# LevelTranslator.net
KiCad netlist of a schematic drawn in Altium Designer
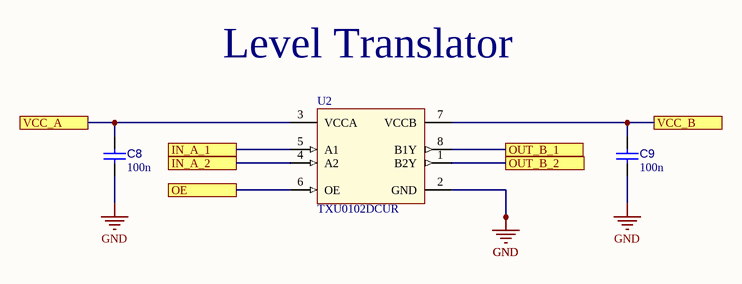
[diagram p0: LevelTranslator.SchDoc]

(export (version "E")
  (design (tool "Eeschema 10.0.6"))
  (components
    (comp (ref "C8")
      (value "100n")
      (footprint "C_1608[0603]")
      (description "Capacitor type 1")
      (fields (field (name "TOLERANCE") "10%") (field (name "Comment") "CAP CER 100nF 50V 0603"))
      (libsource (lib "TEP-AltiumLib-Passives-RLC") (part "capacitor"))
    )
    (comp (ref "C9")
      (value "100n")
      (footprint "C_1608[0603]")
      (description "Capacitor type 1")
      (fields (field (name "TOLERANCE") "10%") (field (name "Comment") "CAP CER 100nF 50V 0603"))
      (libsource (lib "TEP-AltiumLib-Passives-RLC") (part "capacitor"))
    )
    (comp (ref "U2")
      (value "TXU0102DCUR")
      (footprint "U_VSSOP50P310X200X90-8N")
      (description "Two channel fixed-direction level shifter 8-VSSOP")
      (libsource (lib "TEP-AltiumLib-ICs") (part "U_TXU0102DCU"))
    )
  )
  (nets
    (net (code "1") (name "/IN_A_1") (class "Default")
      (node (ref "U2") (pin "5") (pinfunction "A1_5") (pintype "input"))
    )
    (net (code "2") (name "/IN_A_2") (class "Default")
      (node (ref "U2") (pin "4") (pinfunction "A2_4") (pintype "input"))
    )
    (net (code "3") (name "/OE") (class "Default")
      (node (ref "U2") (pin "6") (pinfunction "OE_6") (pintype "input"))
    )
    (net (code "4") (name "/OUT_B_1") (class "Default")
      (node (ref "U2") (pin "8") (pinfunction "B1Y_8") (pintype "output"))
    )
    (net (code "5") (name "/OUT_B_2") (class "Default")
      (node (ref "U2") (pin "1") (pinfunction "B2Y_1") (pintype "output"))
    )
    (net (code "6") (name "/VCC_A") (class "Default")
      (node (ref "C8") (pin "2") (pinfunction "2_2") (pintype "passive"))
      (node (ref "U2") (pin "3") (pinfunction "VCCA_3") (pintype "power_in"))
    )
    (net (code "7") (name "/VCC_B") (class "Default")
      (node (ref "C9") (pin "2") (pinfunction "2_2") (pintype "passive"))
      (node (ref "U2") (pin "7") (pinfunction "VCCB_7") (pintype "power_in"))
    )
    (net (code "8") (name "GND") (class "Default")
      (node (ref "C8") (pin "1") (pinfunction "1_1") (pintype "passive"))
      (node (ref "C9") (pin "1") (pinfunction "1_1") (pintype "passive"))
      (node (ref "U2") (pin "2") (pinfunction "GND_2") (pintype "power_in"))
    )
  )
)
